# Microcontroller.net
KiCad netlist of a schematic drawn in Altium Designer
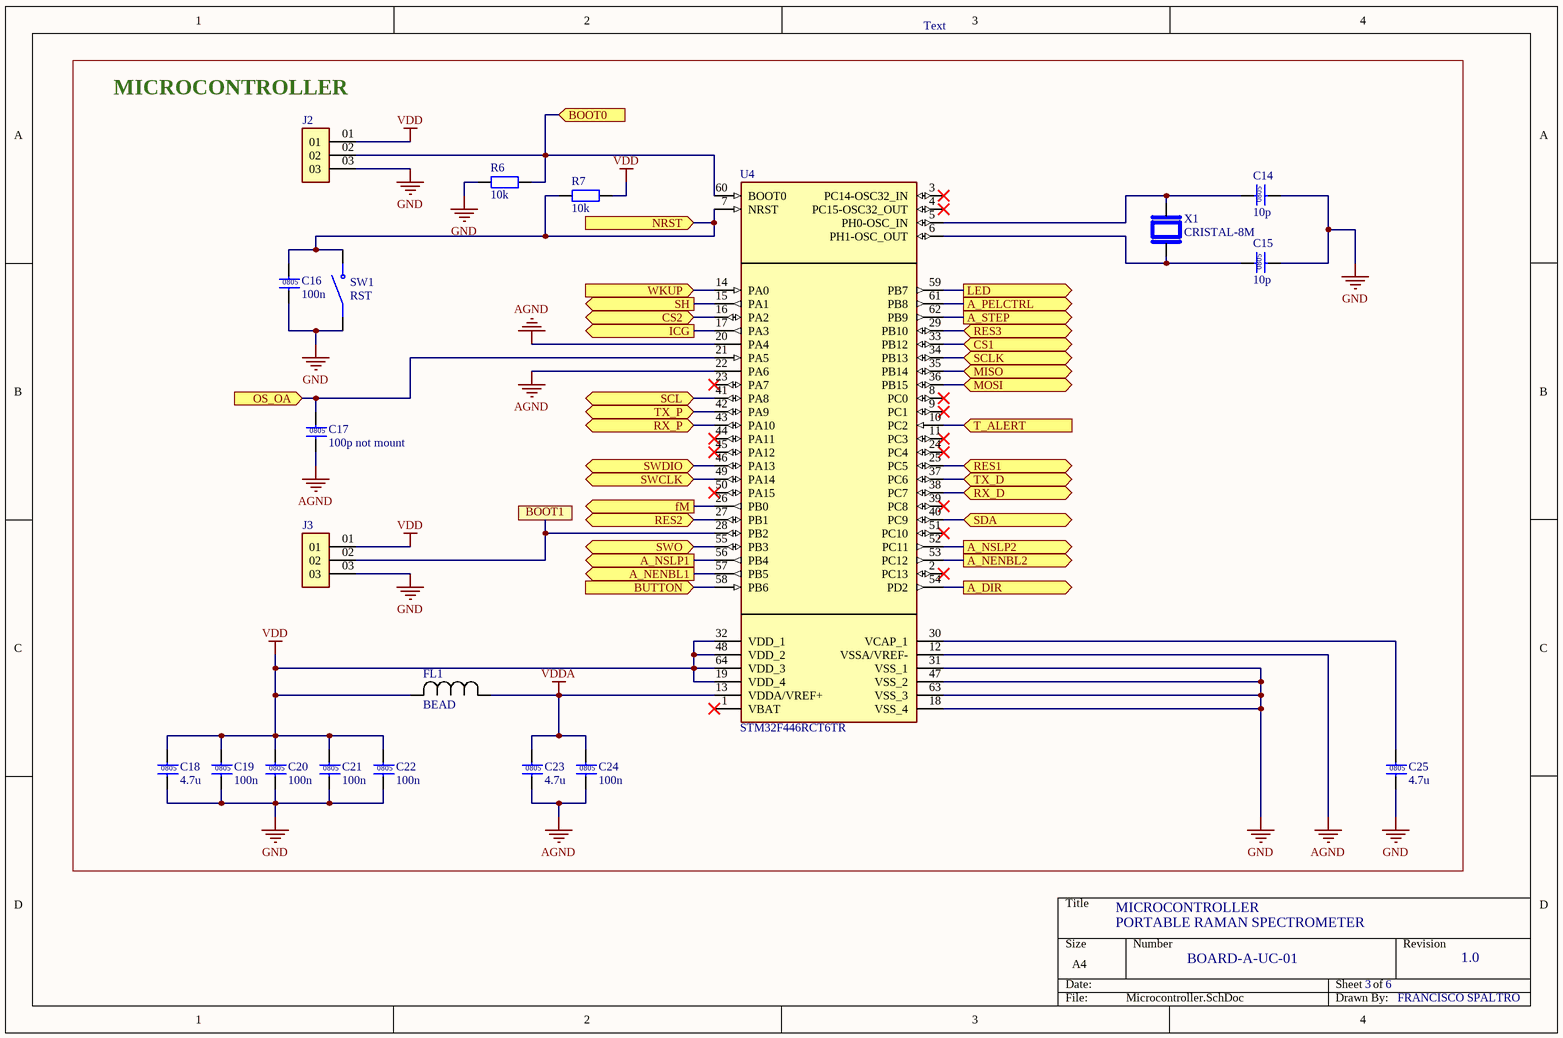
[diagram p0: Microcontroller.SchDoc]

(export (version "E")
  (design (tool "Eeschema 10.0.6"))
  (components
    (comp (ref "C14")
      (value "10p")
      (footprint "RES_0805")
      (description "Kemet C0805C100J5GACTU")
      (libsource (lib "Components") (part "CAP_0805"))
    )
    (comp (ref "C15")
      (value "10p")
      (footprint "RES_0805")
      (description "Kemet C0805C100J5GACTU")
      (libsource (lib "Components") (part "CAP_0805"))
    )
    (comp (ref "C16")
      (value "100n")
      (footprint "RES_0805")
      (description "Kemet C0805C104K3RAC7800")
      (libsource (lib "Components") (part "CAP_0805"))
    )
    (comp (ref "C17")
      (value "100p not mount")
      (footprint "RES_0805")
      (description "Kemet C0805C101J5GACTU")
      (libsource (lib "Components") (part "CAP_0805"))
    )
    (comp (ref "C18")
      (value "4.7u")
      (footprint "RES_0805")
      (description "Samsung CL21B475KOFNNNE")
      (libsource (lib "Components") (part "CAP_0805"))
    )
    (comp (ref "C19")
      (value "100n")
      (footprint "RES_0805")
      (description "Kemet C0805C104K3RAC7800")
      (libsource (lib "Components") (part "CAP_0805"))
    )
    (comp (ref "C20")
      (value "100n")
      (footprint "RES_0805")
      (description "Kemet C0805C104K3RAC7800")
      (libsource (lib "Components") (part "CAP_0805"))
    )
    (comp (ref "C21")
      (value "100n")
      (footprint "RES_0805")
      (description "Kemet C0805C104K3RAC7800")
      (libsource (lib "Components") (part "CAP_0805"))
    )
    (comp (ref "C22")
      (value "100n")
      (footprint "RES_0805")
      (description "Kemet C0805C104K3RAC7800")
      (libsource (lib "Components") (part "CAP_0805"))
    )
    (comp (ref "C23")
      (value "4.7u")
      (footprint "RES_0805")
      (description "Samsung CL21B475KOFNNNE")
      (libsource (lib "Components") (part "CAP_0805"))
    )
    (comp (ref "C24")
      (value "100n")
      (footprint "RES_0805")
      (description "Kemet C0805C104K3RAC7800")
      (libsource (lib "Components") (part "CAP_0805"))
    )
    (comp (ref "C25")
      (value "4.7u")
      (footprint "RES_0805")
      (description "Samsung CL21B475KOFNNNE")
      (libsource (lib "Components") (part "CAP_0805"))
    )
    (comp (ref "FL1")
      (value "BEAD")
      (footprint "IND_1608_TDK-M")
      (description "INDUCTOR; SMT (0603); FERRITE-BEAD; 600; TOL=+/-25%; 0.5A; -55 DEGC TO +125 DEGC")
      (fields
        (field (name "MANUFACTURER_PART_NUMBER") "MMZ1608B601CTAH0")
        (field (name "COPYRIGHT") "Copyright (C) 2025 Ultra Librarian. All rights reserved.")
      )
      (libsource (lib "Components") (part "MMZ1608B601CTAH0"))
    )
    (comp (ref "J2")
      (value "PIN_HEADER_3")
      (footprint "GEN_PIN3")
      (description "Generic 40 mils drill size, 100 mils step")
      (fields (field (name "MF") "Samtec Inc.") (field (name "MP") "TS-103-T-A"))
      (libsource (lib "Components") (part "PIN_HEADER_3"))
    )
    (comp (ref "J3")
      (value "PIN_HEADER_3")
      (footprint "GEN_PIN3")
      (description "Generic 40 mils drill size, 100 mils step")
      (fields (field (name "MF") "Samtec Inc.") (field (name "MP") "TS-103-T-A"))
      (libsource (lib "Components") (part "PIN_HEADER_3"))
    )
    (comp (ref "R6")
      (value "10k")
      (footprint "RES_0805")
      (description "Generic Capacitor")
      (libsource (lib "Components") (part "RES_0805"))
    )
    (comp (ref "R7")
      (value "10k")
      (footprint "RES_0805")
      (description "Generic Capacitor")
      (libsource (lib "Components") (part "RES_0805"))
    )
    (comp (ref "SW1")
      (value "RST")
      (footprint "Components:SW_B3U-1000P")
      (description "Switch Tactile N.O. SPST Round Button Gull Wing 0.05A 12VDC 1.5N SMD Embossed T/R")
      (fields (field (name "MP") "B3U-1000P"))
      (libsource (lib "Components") (part "SW-B3U-1000P"))
    )
    (comp (ref "U4")
      (value "STM32F446RCT6TR")
      (footprint "QFP50P1200X1200X160-64N")
      (fields (field (name "MF") "STMicroelectronics"))
      (libsource (lib "CI") (part "STM32F446RCT6TR"))
    )
    (comp (ref "X1")
      (value "CRISTAL-8M")
      (footprint "XTALDFN320X250X100-2N")
      (description "8 MHz ±20ppm Crystal 8pF 500 Ohms 2-SMD, No Lead")
      (fields (field (name "MF") "NDK America, Inc.") (field (name "MP") "CG04874-8M"))
      (libsource (lib "CompPas") (part "CRISTAL-CG04874-8M"))
    )
  )
  (nets
    (net (code "1") (name "/A_DIR") (class "Default")
      (node (ref "U4") (pin "54") (pinfunction "PD2_54") (pintype "output"))
    )
    (net (code "2") (name "/A_NENBL1") (class "Default")
      (node (ref "U4") (pin "57") (pinfunction "PB5_57") (pintype "output"))
    )
    (net (code "3") (name "/A_NENBL2") (class "Default")
      (node (ref "U4") (pin "53") (pinfunction "PC12_53") (pintype "output"))
    )
    (net (code "4") (name "/A_NSLP1") (class "Default")
      (node (ref "U4") (pin "56") (pinfunction "PB4_56") (pintype "output"))
    )
    (net (code "5") (name "/A_NSLP2") (class "Default")
      (node (ref "U4") (pin "52") (pinfunction "PC11_52") (pintype "output"))
    )
    (net (code "6") (name "/A_PELCTRL") (class "Default")
      (node (ref "U4") (pin "61") (pinfunction "PB8_61") (pintype "output"))
    )
    (net (code "7") (name "/A_STEP") (class "Default")
      (node (ref "U4") (pin "62") (pinfunction "PB9_62") (pintype "output"))
    )
    (net (code "8") (name "/BOOT0") (class "Default")
      (node (ref "J2") (pin "02") (pinfunction "02_02") (pintype "passive"))
      (node (ref "R6") (pin "1") (pinfunction "1_1") (pintype "passive"))
      (node (ref "U4") (pin "60") (pinfunction "BOOT0_60") (pintype "input"))
    )
    (net (code "9") (name "/BOOT1") (class "Default")
      (node (ref "J3") (pin "02") (pinfunction "02_02") (pintype "passive"))
      (node (ref "U4") (pin "28") (pinfunction "PB2_28") (pintype "bidirectional"))
    )
    (net (code "10") (name "/BUTTON") (class "Default")
      (node (ref "U4") (pin "58") (pinfunction "PB6_58") (pintype "input"))
    )
    (net (code "11") (name "/CS1") (class "Default")
      (node (ref "U4") (pin "33") (pinfunction "PB12_33") (pintype "bidirectional"))
    )
    (net (code "12") (name "/CS2") (class "Default")
      (node (ref "U4") (pin "16") (pinfunction "PA2_16") (pintype "bidirectional"))
    )
    (net (code "13") (name "/ICG") (class "Default")
      (node (ref "U4") (pin "17") (pinfunction "PA3_17") (pintype "output"))
    )
    (net (code "14") (name "/LED") (class "Default")
      (node (ref "U4") (pin "59") (pinfunction "PB7_59") (pintype "output"))
    )
    (net (code "15") (name "/MISO") (class "Default")
      (node (ref "U4") (pin "35") (pinfunction "PB14_35") (pintype "bidirectional"))
    )
    (net (code "16") (name "/MOSI") (class "Default")
      (node (ref "U4") (pin "36") (pinfunction "PB15_36") (pintype "bidirectional"))
    )
    (net (code "17") (name "/NRST") (class "Default")
      (node (ref "C16") (pin "1") (pinfunction "1_1") (pintype "passive"))
      (node (ref "R7") (pin "1") (pinfunction "1_1") (pintype "passive"))
      (node (ref "SW1") (pin "2") (pinfunction "2_2") (pintype "passive"))
      (node (ref "U4") (pin "7") (pinfunction "NRST_7") (pintype "input"))
    )
    (net (code "18") (name "/OS_OA") (class "Default")
      (node (ref "C17") (pin "1") (pinfunction "1_1") (pintype "passive"))
      (node (ref "U4") (pin "21") (pinfunction "PA5_21") (pintype "input"))
    )
    (net (code "19") (name "/RES1") (class "Default")
      (node (ref "U4") (pin "25") (pinfunction "PC5_25") (pintype "bidirectional"))
    )
    (net (code "20") (name "/RES2") (class "Default")
      (node (ref "U4") (pin "27") (pinfunction "PB1_27") (pintype "bidirectional"))
    )
    (net (code "21") (name "/RES3") (class "Default")
      (node (ref "U4") (pin "29") (pinfunction "PB10_29") (pintype "bidirectional"))
    )
    (net (code "22") (name "/RX_D") (class "Default")
      (node (ref "U4") (pin "38") (pinfunction "PC7_38") (pintype "bidirectional"))
    )
    (net (code "23") (name "/RX_P") (class "Default")
      (node (ref "U4") (pin "43") (pinfunction "PA10_43") (pintype "bidirectional"))
    )
    (net (code "24") (name "/SCL") (class "Default")
      (node (ref "U4") (pin "41") (pinfunction "PA8_41") (pintype "bidirectional"))
    )
    (net (code "25") (name "/SCLK") (class "Default")
      (node (ref "U4") (pin "34") (pinfunction "PB13_34") (pintype "bidirectional"))
    )
    (net (code "26") (name "/SDA") (class "Default")
      (node (ref "U4") (pin "40") (pinfunction "PC9_40") (pintype "bidirectional"))
    )
    (net (code "27") (name "/SH") (class "Default")
      (node (ref "U4") (pin "15") (pinfunction "PA1_15") (pintype "output"))
    )
    (net (code "28") (name "/SWCLK") (class "Default")
      (node (ref "U4") (pin "49") (pinfunction "PA14_49") (pintype "bidirectional"))
    )
    (net (code "29") (name "/SWDIO") (class "Default")
      (node (ref "U4") (pin "46") (pinfunction "PA13_46") (pintype "bidirectional"))
    )
    (net (code "30") (name "/SWO") (class "Default")
      (node (ref "U4") (pin "55") (pinfunction "PB3_55") (pintype "bidirectional"))
    )
    (net (code "31") (name "/TX_D") (class "Default")
      (node (ref "U4") (pin "37") (pinfunction "PC6_37") (pintype "bidirectional"))
    )
    (net (code "32") (name "/TX_P") (class "Default")
      (node (ref "U4") (pin "42") (pinfunction "PA9_42") (pintype "bidirectional"))
    )
    (net (code "33") (name "/T_ALERT") (class "Default")
      (node (ref "U4") (pin "10") (pinfunction "PC2_10") (pintype "input"))
    )
    (net (code "34") (name "/WKUP") (class "Default")
      (node (ref "U4") (pin "14") (pinfunction "PA0_14") (pintype "input"))
    )
    (net (code "35") (name "/fM") (class "Default")
      (node (ref "U4") (pin "26") (pinfunction "PB0_26") (pintype "output"))
    )
    (net (code "36") (name "AGND") (class "Default")
      (node (ref "C17") (pin "2") (pinfunction "2_2") (pintype "passive"))
      (node (ref "C23") (pin "2") (pinfunction "2_2") (pintype "passive"))
      (node (ref "C24") (pin "2") (pinfunction "2_2") (pintype "passive"))
      (node (ref "U4") (pin "12") (pinfunction "VSSA/VREF-_12") (pintype "passive"))
      (node (ref "U4") (pin "20") (pinfunction "PA4_20") (pintype "passive"))
      (node (ref "U4") (pin "22") (pinfunction "PA6_22") (pintype "passive"))
    )
    (net (code "37") (name "GND") (class "Default")
      (node (ref "C14") (pin "2") (pinfunction "2_2") (pintype "passive"))
      (node (ref "C15") (pin "2") (pinfunction "2_2") (pintype "passive"))
      (node (ref "C16") (pin "2") (pinfunction "2_2") (pintype "passive"))
      (node (ref "C18") (pin "2") (pinfunction "2_2") (pintype "passive"))
      (node (ref "C19") (pin "2") (pinfunction "2_2") (pintype "passive"))
      (node (ref "C20") (pin "2") (pinfunction "2_2") (pintype "passive"))
      (node (ref "C21") (pin "2") (pinfunction "2_2") (pintype "passive"))
      (node (ref "C22") (pin "2") (pinfunction "2_2") (pintype "passive"))
      (node (ref "C25") (pin "2") (pinfunction "2_2") (pintype "passive"))
      (node (ref "J2") (pin "03") (pinfunction "03_03") (pintype "passive"))
      (node (ref "J3") (pin "03") (pinfunction "03_03") (pintype "passive"))
      (node (ref "R6") (pin "2") (pinfunction "2_2") (pintype "passive"))
      (node (ref "SW1") (pin "1") (pinfunction "1_1") (pintype "passive"))
      (node (ref "U4") (pin "18") (pinfunction "VSS_4_18") (pintype "power_in"))
      (node (ref "U4") (pin "31") (pinfunction "VSS_1_31") (pintype "power_in"))
      (node (ref "U4") (pin "47") (pinfunction "VSS_2_47") (pintype "power_in"))
      (node (ref "U4") (pin "63") (pinfunction "VSS_3_63") (pintype "power_in"))
    )
    (net (code "38") (name "Net-(U4-PH0-OSC_IN)") (class "Default")
      (node (ref "C14") (pin "1") (pinfunction "1_1") (pintype "passive"))
      (node (ref "U4") (pin "5") (pinfunction "PH0-OSC_IN_5") (pintype "bidirectional"))
      (node (ref "X1") (pin "2") (pinfunction "2_2") (pintype "passive"))
    )
    (net (code "39") (name "Net-(U4-PH1-OSC_OUT)") (class "Default")
      (node (ref "C15") (pin "1") (pinfunction "1_1") (pintype "passive"))
      (node (ref "U4") (pin "6") (pinfunction "PH1-OSC_OUT_6") (pintype "bidirectional"))
      (node (ref "X1") (pin "1") (pinfunction "1_1") (pintype "passive"))
    )
    (net (code "40") (name "Net-(U4-VCAP_1)") (class "Default")
      (node (ref "C25") (pin "1") (pinfunction "1_1") (pintype "passive"))
      (node (ref "U4") (pin "30") (pinfunction "VCAP_1_30") (pintype "power_in"))
    )
    (net (code "41") (name "VDD") (class "Default")
      (node (ref "C18") (pin "1") (pinfunction "1_1") (pintype "passive"))
      (node (ref "C19") (pin "1") (pinfunction "1_1") (pintype "passive"))
      (node (ref "C20") (pin "1") (pinfunction "1_1") (pintype "passive"))
      (node (ref "C21") (pin "1") (pinfunction "1_1") (pintype "passive"))
      (node (ref "C22") (pin "1") (pinfunction "1_1") (pintype "passive"))
      (node (ref "FL1") (pin "2") (pinfunction "2_2") (pintype "passive"))
      (node (ref "J2") (pin "01") (pinfunction "01_01") (pintype "passive"))
      (node (ref "J3") (pin "01") (pinfunction "01_01") (pintype "passive"))
      (node (ref "R7") (pin "2") (pinfunction "2_2") (pintype "passive"))
      (node (ref "U4") (pin "19") (pinfunction "VDD_4_19") (pintype "power_in"))
      (node (ref "U4") (pin "32") (pinfunction "VDD_1_32") (pintype "power_in"))
      (node (ref "U4") (pin "48") (pinfunction "VDD_2_48") (pintype "power_in"))
      (node (ref "U4") (pin "64") (pinfunction "VDD_3_64") (pintype "power_in"))
    )
    (net (code "42") (name "VDDA") (class "Default")
      (node (ref "C23") (pin "1") (pinfunction "1_1") (pintype "passive"))
      (node (ref "C24") (pin "1") (pinfunction "1_1") (pintype "passive"))
      (node (ref "FL1") (pin "1") (pinfunction "1_1") (pintype "passive"))
      (node (ref "U4") (pin "13") (pinfunction "VDDA/VREF+_13") (pintype "power_in"))
    )
    (net (code "43") (name "unconnected-(U4-PA7-Pad23)") (class "Default")
      (node (ref "U4") (pin "23") (pinfunction "PA7_23") (pintype "bidirectional+no_connect"))
    )
    (net (code "44") (name "unconnected-(U4-PA11-Pad44)") (class "Default")
      (node (ref "U4") (pin "44") (pinfunction "PA11_44") (pintype "bidirectional+no_connect"))
    )
    (net (code "45") (name "unconnected-(U4-PA12-Pad45)") (class "Default")
      (node (ref "U4") (pin "45") (pinfunction "PA12_45") (pintype "bidirectional+no_connect"))
    )
    (net (code "46") (name "unconnected-(U4-PA15-Pad50)") (class "Default")
      (node (ref "U4") (pin "50") (pinfunction "PA15_50") (pintype "bidirectional+no_connect"))
    )
    (net (code "47") (name "unconnected-(U4-PC0-Pad8)") (class "Default")
      (node (ref "U4") (pin "8") (pinfunction "PC0_8") (pintype "bidirectional+no_connect"))
    )
    (net (code "48") (name "unconnected-(U4-PC1-Pad9)") (class "Default")
      (node (ref "U4") (pin "9") (pinfunction "PC1_9") (pintype "bidirectional+no_connect"))
    )
    (net (code "49") (name "unconnected-(U4-PC3-Pad11)") (class "Default")
      (node (ref "U4") (pin "11") (pinfunction "PC3_11") (pintype "bidirectional+no_connect"))
    )
    (net (code "50") (name "unconnected-(U4-PC4-Pad24)") (class "Default")
      (node (ref "U4") (pin "24") (pinfunction "PC4_24") (pintype "bidirectional+no_connect"))
    )
    (net (code "51") (name "unconnected-(U4-PC8-Pad39)") (class "Default")
      (node (ref "U4") (pin "39") (pinfunction "PC8_39") (pintype "bidirectional+no_connect"))
    )
    (net (code "52") (name "unconnected-(U4-PC10-Pad51)") (class "Default")
      (node (ref "U4") (pin "51") (pinfunction "PC10_51") (pintype "bidirectional+no_connect"))
    )
    (net (code "53") (name "unconnected-(U4-PC13-Pad2)") (class "Default")
      (node (ref "U4") (pin "2") (pinfunction "PC13_2") (pintype "bidirectional+no_connect"))
    )
    (net (code "54") (name "unconnected-(U4-PC14-OSC32_IN-Pad3)") (class "Default")
      (node (ref "U4") (pin "3") (pinfunction "PC14-OSC32_IN_3") (pintype "bidirectional+no_connect"))
    )
    (net (code "55") (name "unconnected-(U4-PC15-OSC32_OUT-Pad4)") (class "Default")
      (node (ref "U4") (pin "4") (pinfunction "PC15-OSC32_OUT_4") (pintype "bidirectional+no_connect"))
    )
    (net (code "56") (name "unconnected-(U4-VBAT-Pad1)") (class "Default")
      (node (ref "U4") (pin "1") (pinfunction "VBAT_1") (pintype "power_in+no_connect"))
    )
  )
)
